# Populated_PLG_sensor_Flash.net
KiCad netlist of a schematic drawn in EAGLE
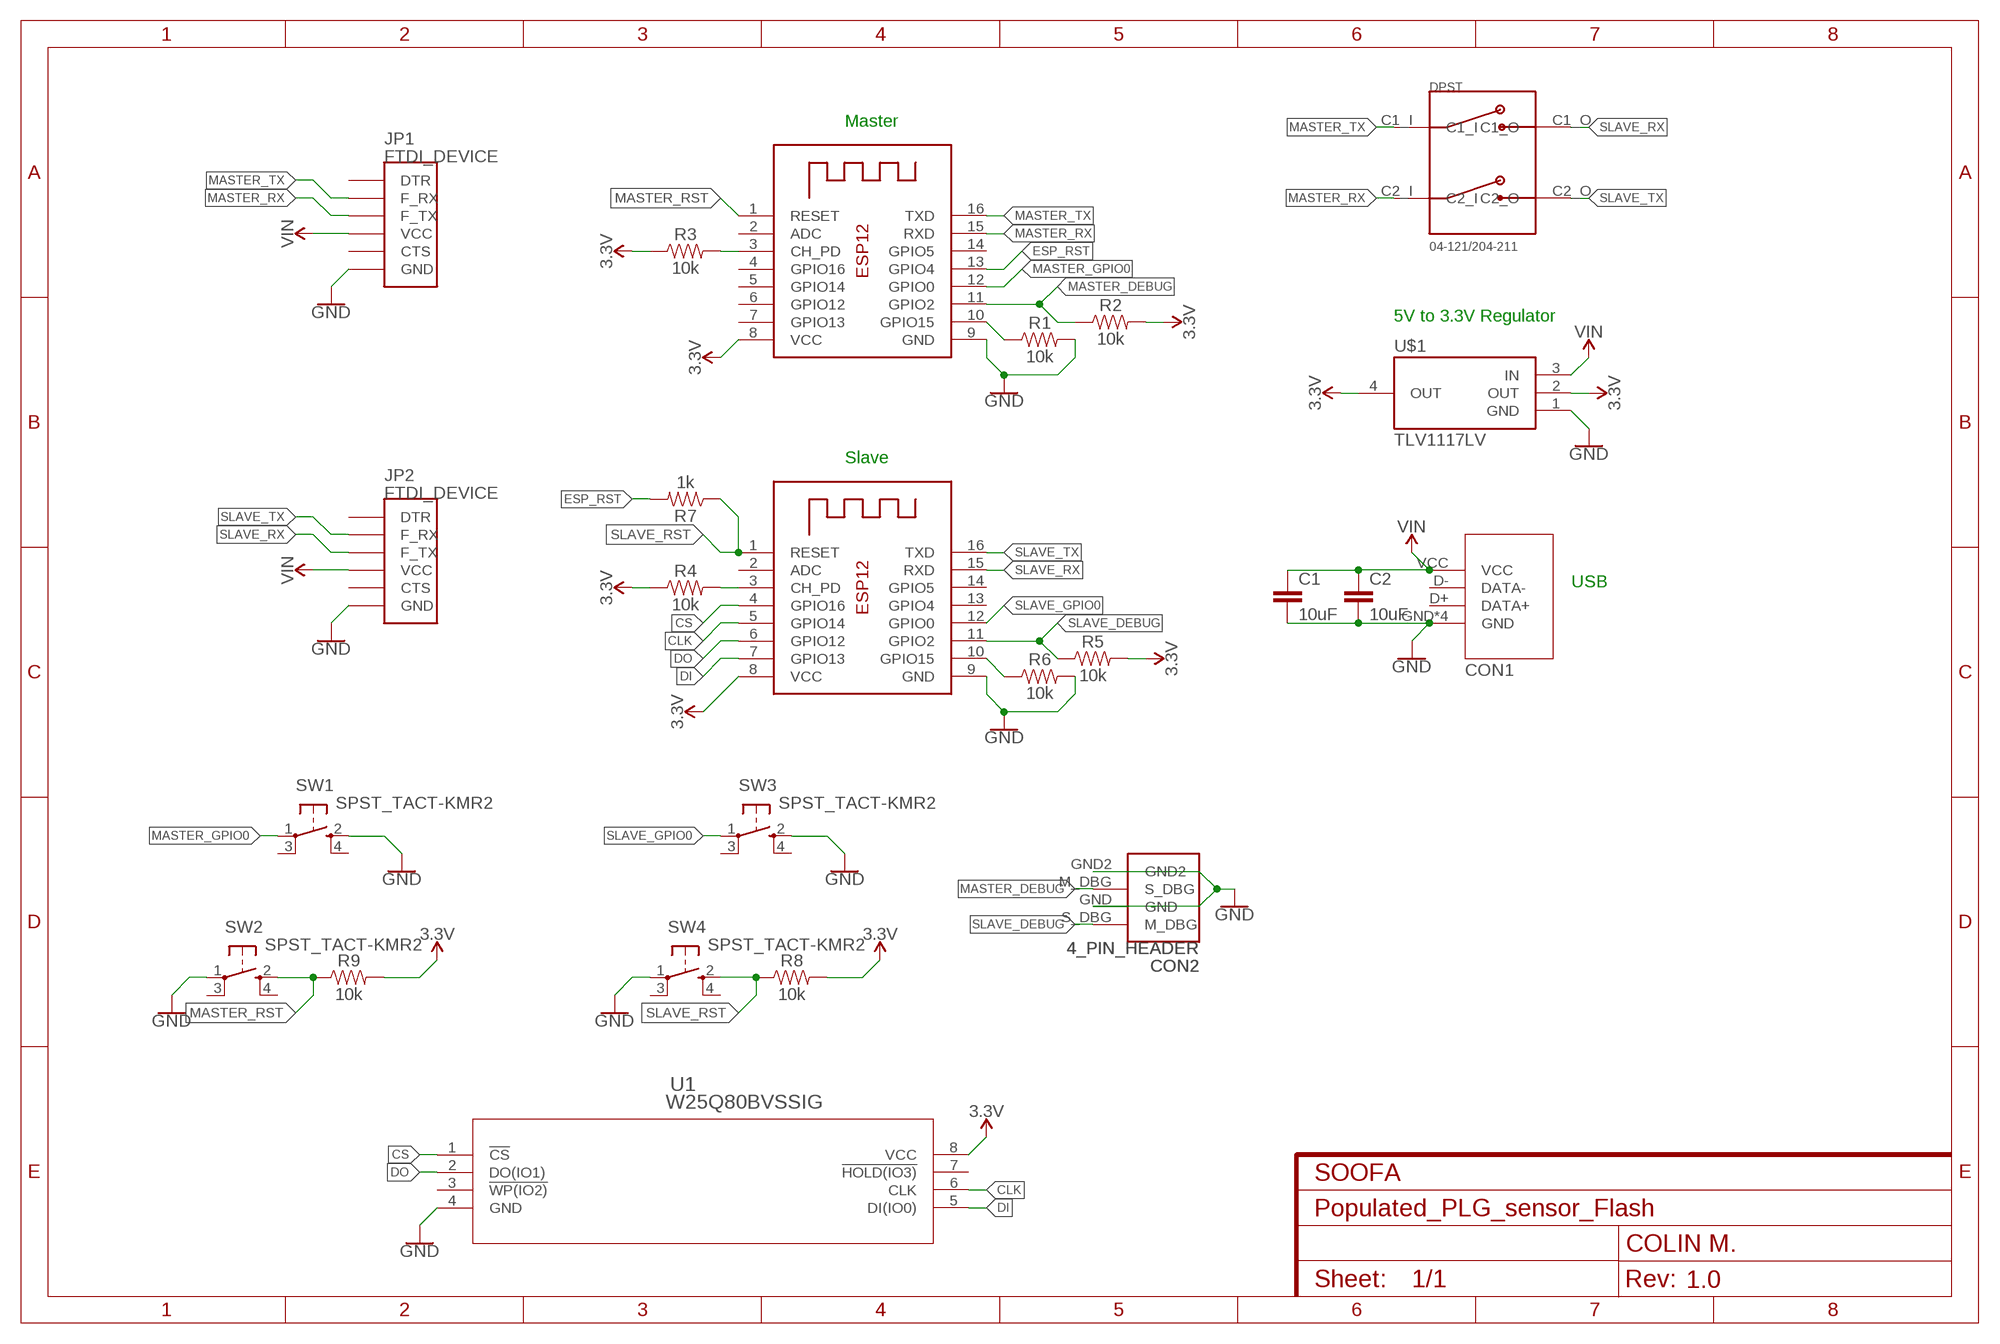
[diagram p0: schematic, sheet 1]

(export (version "E")
  (design (tool "Eeschema 10.0.6"))
  (components
    (comp (ref "C1")
      (value "10uF")
      (footprint "eagle-import:0603")
      (libsource (lib "eagle-import") (part "10UF-0603-6.3V-20%"))
    )
    (comp (ref "C2")
      (value "10uF")
      (footprint "eagle-import:0603")
      (libsource (lib "eagle-import") (part "10UF-0603-6.3V-20%"))
    )
    (comp (ref "CON1")
      (value "USB_MOLEX_0480372200")
      (footprint "eagle-import:USB_MOLEX_0480372200")
      (libsource (lib "eagle-import") (part "USB_MOLEX_0480372200"))
    )
    (comp (ref "CON2")
      (value "4_PIN_HEADER")
      (footprint "eagle-import:22-23-2041")
      (libsource (lib "eagle-import") (part "4_PIN_HEADER"))
    )
    (comp (ref "DPST1")
      (value "DPST_1POS")
      (footprint "eagle-import:DPST_1POS")
      (libsource (lib "eagle-import") (part "DPST_1POS"))
    )
    (comp (ref "JP1")
      (value "FTDI_DEVICE")
      (footprint "eagle-import:FTDI_DEVICE_SIDE")
      (libsource (lib "eagle-import") (part "FTDI_DEVICE"))
    )
    (comp (ref "JP2")
      (value "FTDI_DEVICE")
      (footprint "eagle-import:FTDI_DEVICE_SIDE")
      (libsource (lib "eagle-import") (part "FTDI_DEVICE"))
    )
    (comp (ref "R1")
      (value "10k")
      (footprint "eagle-import:0603")
      (libsource (lib "eagle-import") (part "10KOHM-0603-1/10W-1%"))
    )
    (comp (ref "R2")
      (value "10k")
      (footprint "eagle-import:0603")
      (libsource (lib "eagle-import") (part "10KOHM-0603-1/10W-1%"))
    )
    (comp (ref "R3")
      (value "10k")
      (footprint "eagle-import:0603")
      (libsource (lib "eagle-import") (part "10KOHM-0603-1/10W-1%"))
    )
    (comp (ref "R4")
      (value "10k")
      (footprint "eagle-import:0603")
      (libsource (lib "eagle-import") (part "10KOHM-0603-1/10W-1%"))
    )
    (comp (ref "R5")
      (value "10k")
      (footprint "eagle-import:0603")
      (libsource (lib "eagle-import") (part "10KOHM-0603-1/10W-1%"))
    )
    (comp (ref "R6")
      (value "10k")
      (footprint "eagle-import:0603")
      (libsource (lib "eagle-import") (part "10KOHM-0603-1/10W-1%"))
    )
    (comp (ref "R7")
      (value "1k")
      (footprint "eagle-import:0603")
      (libsource (lib "eagle-import") (part "1KOHM-0603-1/10W-1%"))
    )
    (comp (ref "R8")
      (value "10k")
      (footprint "eagle-import:0603")
      (libsource (lib "eagle-import") (part "10KOHM-0603-1/10W-1%"))
    )
    (comp (ref "R9")
      (value "10k")
      (footprint "eagle-import:0603")
      (libsource (lib "eagle-import") (part "10KOHM-0603-1/10W-1%"))
    )
    (comp (ref "SW1")
      (value "SPST_TACT-KMR2")
      (footprint "eagle-import:KMR2")
      (libsource (lib "eagle-import") (part "SPST_TACT-KMR2"))
    )
    (comp (ref "SW2")
      (value "SPST_TACT-KMR2")
      (footprint "eagle-import:KMR2")
      (libsource (lib "eagle-import") (part "SPST_TACT-KMR2"))
    )
    (comp (ref "SW3")
      (value "SPST_TACT-KMR2")
      (footprint "eagle-import:KMR2")
      (libsource (lib "eagle-import") (part "SPST_TACT-KMR2"))
    )
    (comp (ref "SW4")
      (value "SPST_TACT-KMR2")
      (footprint "eagle-import:KMR2")
      (libsource (lib "eagle-import") (part "SPST_TACT-KMR2"))
    )
    (comp (ref "U$1")
      (value "TLV1117LV")
      (footprint "eagle-import:SOT223")
      (libsource (lib "eagle-import") (part "TLV1117LV"))
    )
    (comp (ref "U1")
      (value "W25Q80BVSSIG")
      (footprint "eagle-import:WIN_SS-8")
      (libsource (lib "eagle-import") (part "W25Q80BVSSIG"))
    )
    (comp (ref "X1")
      (value "ESP-12")
      (footprint "eagle-import:ESP-12")
      (libsource (lib "eagle-import") (part "ESP-12"))
    )
    (comp (ref "X2")
      (value "ESP-12")
      (footprint "eagle-import:ESP-12")
      (libsource (lib "eagle-import") (part "ESP-12"))
    )
  )
  (nets
    (net (code "1") (name "3.3V") (class "Default")
      (node (ref "R2") (pin "2") (pinfunction "2_2") (pintype "passive"))
      (node (ref "R3") (pin "1") (pinfunction "1_1") (pintype "passive"))
      (node (ref "R4") (pin "1") (pinfunction "1_1") (pintype "passive"))
      (node (ref "R5") (pin "2") (pinfunction "2_2") (pintype "passive"))
      (node (ref "R8") (pin "2") (pinfunction "2_2") (pintype "passive"))
      (node (ref "R9") (pin "2") (pinfunction "2_2") (pintype "passive"))
      (node (ref "U$1") (pin "2") (pinfunction "OUT_2") (pintype "bidirectional"))
      (node (ref "U$1") (pin "4") (pinfunction "OUT_4") (pintype "bidirectional"))
      (node (ref "U1") (pin "8") (pinfunction "VCC_8") (pintype "power_in"))
      (node (ref "X1") (pin "8") (pinfunction "VCC_8") (pintype "power_in"))
      (node (ref "X2") (pin "8") (pinfunction "VCC_8") (pintype "power_in"))
    )
    (net (code "2") (name "CLK") (class "Default")
      (node (ref "U1") (pin "6") (pinfunction "CLK_6") (pintype "input"))
      (node (ref "X2") (pin "5") (pinfunction "GPIO14_5") (pintype "bidirectional"))
    )
    (net (code "3") (name "CS") (class "Default")
      (node (ref "U1") (pin "1") (pinfunction "~{CS}_1") (pintype "input"))
      (node (ref "X2") (pin "4") (pinfunction "GPIO16_4") (pintype "bidirectional"))
    )
    (net (code "4") (name "DI") (class "Default")
      (node (ref "U1") (pin "5") (pinfunction "DI(IO0)_5") (pintype "bidirectional"))
      (node (ref "X2") (pin "7") (pinfunction "GPIO13_7") (pintype "bidirectional"))
    )
    (net (code "5") (name "DO") (class "Default")
      (node (ref "U1") (pin "2") (pinfunction "DO(IO1)_2") (pintype "bidirectional"))
      (node (ref "X2") (pin "6") (pinfunction "GPIO12_6") (pintype "bidirectional"))
    )
    (net (code "6") (name "ESP_RST") (class "Default")
      (node (ref "R7") (pin "2") (pinfunction "2_2") (pintype "passive"))
      (node (ref "X1") (pin "13") (pinfunction "GPIO4_13") (pintype "bidirectional"))
    )
    (net (code "7") (name "GND") (class "Default")
      (node (ref "C1") (pin "2") (pinfunction "2_2") (pintype "passive"))
      (node (ref "C2") (pin "2") (pinfunction "2_2") (pintype "passive"))
      (node (ref "CON1") (pin "GND") (pinfunction "GND_GND") (pintype "bidirectional"))
      (node (ref "CON1") (pin "GND2") (pinfunction "GND_GND2") (pintype "bidirectional"))
      (node (ref "CON1") (pin "GND3") (pinfunction "GND_GND3") (pintype "bidirectional"))
      (node (ref "CON1") (pin "GND4") (pinfunction "GND_GND4") (pintype "bidirectional"))
      (node (ref "CON2") (pin "GND") (pinfunction "GND_GND") (pintype "bidirectional"))
      (node (ref "CON2") (pin "GND2") (pinfunction "GND2_GND2") (pintype "bidirectional"))
      (node (ref "JP1") (pin "P$6") (pinfunction "GND_P$6") (pintype "bidirectional"))
      (node (ref "JP2") (pin "P$6") (pinfunction "GND_P$6") (pintype "bidirectional"))
      (node (ref "R1") (pin "2") (pinfunction "2_2") (pintype "passive"))
      (node (ref "R6") (pin "2") (pinfunction "2_2") (pintype "passive"))
      (node (ref "SW1") (pin "2") (pinfunction "S_2") (pintype "passive"))
      (node (ref "SW2") (pin "1") (pinfunction "P_1") (pintype "passive"))
      (node (ref "SW3") (pin "2") (pinfunction "S_2") (pintype "passive"))
      (node (ref "SW4") (pin "1") (pinfunction "P_1") (pintype "passive"))
      (node (ref "U$1") (pin "1") (pinfunction "GND_1") (pintype "bidirectional"))
      (node (ref "U1") (pin "4") (pinfunction "GND_4") (pintype "power_in"))
      (node (ref "X1") (pin "9") (pinfunction "GND_9") (pintype "power_in"))
      (node (ref "X2") (pin "9") (pinfunction "GND_9") (pintype "power_in"))
    )
    (net (code "8") (name "MASTER_DEBUG") (class "Default")
      (node (ref "CON2") (pin "M_DBG") (pinfunction "S_DBG_M_DBG") (pintype "bidirectional"))
      (node (ref "R2") (pin "1") (pinfunction "1_1") (pintype "passive"))
      (node (ref "X1") (pin "11") (pinfunction "GPIO2_11") (pintype "bidirectional"))
    )
    (net (code "9") (name "MASTER_GPIO0") (class "Default")
      (node (ref "SW1") (pin "1") (pinfunction "P_1") (pintype "passive"))
      (node (ref "X1") (pin "12") (pinfunction "GPIO0_12") (pintype "bidirectional"))
    )
    (net (code "10") (name "MASTER_RST") (class "Default")
      (node (ref "R9") (pin "1") (pinfunction "1_1") (pintype "passive"))
      (node (ref "SW2") (pin "2") (pinfunction "S_2") (pintype "passive"))
      (node (ref "X1") (pin "1") (pinfunction "RESET_1") (pintype "input"))
    )
    (net (code "11") (name "MASTER_RX") (class "Default")
      (node (ref "DPST1") (pin "C2_I") (pinfunction "C2_I_C2_I") (pintype "bidirectional"))
      (node (ref "JP1") (pin "P$3") (pinfunction "F_TX_P$3") (pintype "bidirectional"))
      (node (ref "X1") (pin "15") (pinfunction "RXD_15") (pintype "input"))
    )
    (net (code "12") (name "MASTER_TX") (class "Default")
      (node (ref "DPST1") (pin "C1_I") (pinfunction "C1_I_C1_I") (pintype "bidirectional"))
      (node (ref "JP1") (pin "P$2") (pinfunction "F_RX_P$2") (pintype "bidirectional"))
      (node (ref "X1") (pin "16") (pinfunction "TXD_16") (pintype "output"))
    )
    (net (code "13") (name "Net-(X1-CH_PD)") (class "Default")
      (node (ref "R3") (pin "2") (pinfunction "2_2") (pintype "passive"))
      (node (ref "X1") (pin "3") (pinfunction "CH_PD_3") (pintype "input"))
    )
    (net (code "14") (name "Net-(X1-GPIO15)") (class "Default")
      (node (ref "R1") (pin "1") (pinfunction "1_1") (pintype "passive"))
      (node (ref "X1") (pin "10") (pinfunction "GPIO15_10") (pintype "bidirectional"))
    )
    (net (code "15") (name "Net-(X2-CH_PD)") (class "Default")
      (node (ref "R4") (pin "2") (pinfunction "2_2") (pintype "passive"))
      (node (ref "X2") (pin "3") (pinfunction "CH_PD_3") (pintype "input"))
    )
    (net (code "16") (name "Net-(X2-GPIO15)") (class "Default")
      (node (ref "R6") (pin "1") (pinfunction "1_1") (pintype "passive"))
      (node (ref "X2") (pin "10") (pinfunction "GPIO15_10") (pintype "bidirectional"))
    )
    (net (code "17") (name "SLAVE_DEBUG") (class "Default")
      (node (ref "CON2") (pin "S_DBG") (pinfunction "M_DBG_S_DBG") (pintype "bidirectional"))
      (node (ref "R5") (pin "1") (pinfunction "1_1") (pintype "passive"))
      (node (ref "X2") (pin "11") (pinfunction "GPIO2_11") (pintype "bidirectional"))
    )
    (net (code "18") (name "SLAVE_GPIO0") (class "Default")
      (node (ref "SW3") (pin "1") (pinfunction "P_1") (pintype "passive"))
      (node (ref "X2") (pin "12") (pinfunction "GPIO0_12") (pintype "bidirectional"))
    )
    (net (code "19") (name "SLAVE_RST") (class "Default")
      (node (ref "R7") (pin "1") (pinfunction "1_1") (pintype "passive"))
      (node (ref "R8") (pin "1") (pinfunction "1_1") (pintype "passive"))
      (node (ref "SW4") (pin "2") (pinfunction "S_2") (pintype "passive"))
      (node (ref "X2") (pin "1") (pinfunction "RESET_1") (pintype "input"))
    )
    (net (code "20") (name "SLAVE_RX") (class "Default")
      (node (ref "DPST1") (pin "C1_O") (pinfunction "C1_O_C1_O") (pintype "bidirectional"))
      (node (ref "JP2") (pin "P$3") (pinfunction "F_TX_P$3") (pintype "bidirectional"))
      (node (ref "X2") (pin "15") (pinfunction "RXD_15") (pintype "input"))
    )
    (net (code "21") (name "SLAVE_TX") (class "Default")
      (node (ref "DPST1") (pin "C2_O") (pinfunction "C2_O_C2_O") (pintype "bidirectional"))
      (node (ref "JP2") (pin "P$2") (pinfunction "F_RX_P$2") (pintype "bidirectional"))
      (node (ref "X2") (pin "16") (pinfunction "TXD_16") (pintype "output"))
    )
    (net (code "22") (name "VIN") (class "Default")
      (node (ref "C1") (pin "1") (pinfunction "1_1") (pintype "passive"))
      (node (ref "C2") (pin "1") (pinfunction "1_1") (pintype "passive"))
      (node (ref "CON1") (pin "VCC") (pinfunction "VCC_VCC") (pintype "bidirectional"))
      (node (ref "JP1") (pin "P$4") (pinfunction "VCC_P$4") (pintype "bidirectional"))
      (node (ref "JP2") (pin "P$4") (pinfunction "VCC_P$4") (pintype "bidirectional"))
      (node (ref "U$1") (pin "3") (pinfunction "IN_3") (pintype "bidirectional"))
    )
    (net (code "23") (name "unconnected-(CON1-DATA+-PadD+)") (class "Default")
      (node (ref "CON1") (pin "D+") (pinfunction "DATA+_D+") (pintype "bidirectional"))
    )
    (net (code "24") (name "unconnected-(CON1-DATA--PadD-)") (class "Default")
      (node (ref "CON1") (pin "D-") (pinfunction "DATA-_D-") (pintype "bidirectional"))
    )
    (net (code "25") (name "unconnected-(JP1-CTS-PadP$5)") (class "Default")
      (node (ref "JP1") (pin "P$5") (pinfunction "CTS_P$5") (pintype "bidirectional"))
    )
    (net (code "26") (name "unconnected-(JP1-DTR-PadP$1)") (class "Default")
      (node (ref "JP1") (pin "P$1") (pinfunction "DTR_P$1") (pintype "bidirectional"))
    )
    (net (code "27") (name "unconnected-(JP2-CTS-PadP$5)") (class "Default")
      (node (ref "JP2") (pin "P$5") (pinfunction "CTS_P$5") (pintype "bidirectional"))
    )
    (net (code "28") (name "unconnected-(JP2-DTR-PadP$1)") (class "Default")
      (node (ref "JP2") (pin "P$1") (pinfunction "DTR_P$1") (pintype "bidirectional"))
    )
    (net (code "29") (name "unconnected-(SW1-P1-Pad3)") (class "Default")
      (node (ref "SW1") (pin "3") (pinfunction "P1_3") (pintype "passive"))
    )
    (net (code "30") (name "unconnected-(SW1-S1-Pad4)") (class "Default")
      (node (ref "SW1") (pin "4") (pinfunction "S1_4") (pintype "passive"))
    )
    (net (code "31") (name "unconnected-(SW2-P1-Pad3)") (class "Default")
      (node (ref "SW2") (pin "3") (pinfunction "P1_3") (pintype "passive"))
    )
    (net (code "32") (name "unconnected-(SW2-S1-Pad4)") (class "Default")
      (node (ref "SW2") (pin "4") (pinfunction "S1_4") (pintype "passive"))
    )
    (net (code "33") (name "unconnected-(SW3-P1-Pad3)") (class "Default")
      (node (ref "SW3") (pin "3") (pinfunction "P1_3") (pintype "passive"))
    )
    (net (code "34") (name "unconnected-(SW3-S1-Pad4)") (class "Default")
      (node (ref "SW3") (pin "4") (pinfunction "S1_4") (pintype "passive"))
    )
    (net (code "35") (name "unconnected-(SW4-P1-Pad3)") (class "Default")
      (node (ref "SW4") (pin "3") (pinfunction "P1_3") (pintype "passive"))
    )
    (net (code "36") (name "unconnected-(SW4-S1-Pad4)") (class "Default")
      (node (ref "SW4") (pin "4") (pinfunction "S1_4") (pintype "passive"))
    )
    (net (code "37") (name "unconnected-(U1-~{HOLD(IO3})-Pad7)") (class "Default")
      (node (ref "U1") (pin "7") (pinfunction "~{HOLD(IO3})_7") (pintype "bidirectional"))
    )
    (net (code "38") (name "unconnected-(U1-~{WP(IO2})-Pad3)") (class "Default")
      (node (ref "U1") (pin "3") (pinfunction "~{WP(IO2})_3") (pintype "bidirectional"))
    )
    (net (code "39") (name "unconnected-(X1-ADC-Pad2)") (class "Default")
      (node (ref "X1") (pin "2") (pinfunction "ADC_2") (pintype "passive"))
    )
    (net (code "40") (name "unconnected-(X1-GPIO5-Pad14)") (class "Default")
      (node (ref "X1") (pin "14") (pinfunction "GPIO5_14") (pintype "bidirectional"))
    )
    (net (code "41") (name "unconnected-(X1-GPIO12-Pad6)") (class "Default")
      (node (ref "X1") (pin "6") (pinfunction "GPIO12_6") (pintype "bidirectional"))
    )
    (net (code "42") (name "unconnected-(X1-GPIO13-Pad7)") (class "Default")
      (node (ref "X1") (pin "7") (pinfunction "GPIO13_7") (pintype "bidirectional"))
    )
    (net (code "43") (name "unconnected-(X1-GPIO14-Pad5)") (class "Default")
      (node (ref "X1") (pin "5") (pinfunction "GPIO14_5") (pintype "bidirectional"))
    )
    (net (code "44") (name "unconnected-(X1-GPIO16-Pad4)") (class "Default")
      (node (ref "X1") (pin "4") (pinfunction "GPIO16_4") (pintype "bidirectional"))
    )
    (net (code "45") (name "unconnected-(X2-ADC-Pad2)") (class "Default")
      (node (ref "X2") (pin "2") (pinfunction "ADC_2") (pintype "passive"))
    )
    (net (code "46") (name "unconnected-(X2-GPIO4-Pad13)") (class "Default")
      (node (ref "X2") (pin "13") (pinfunction "GPIO4_13") (pintype "bidirectional"))
    )
    (net (code "47") (name "unconnected-(X2-GPIO5-Pad14)") (class "Default")
      (node (ref "X2") (pin "14") (pinfunction "GPIO5_14") (pintype "bidirectional"))
    )
  )
)
